# ADC_channel.net
KiCad netlist of a schematic drawn in Altium Designer
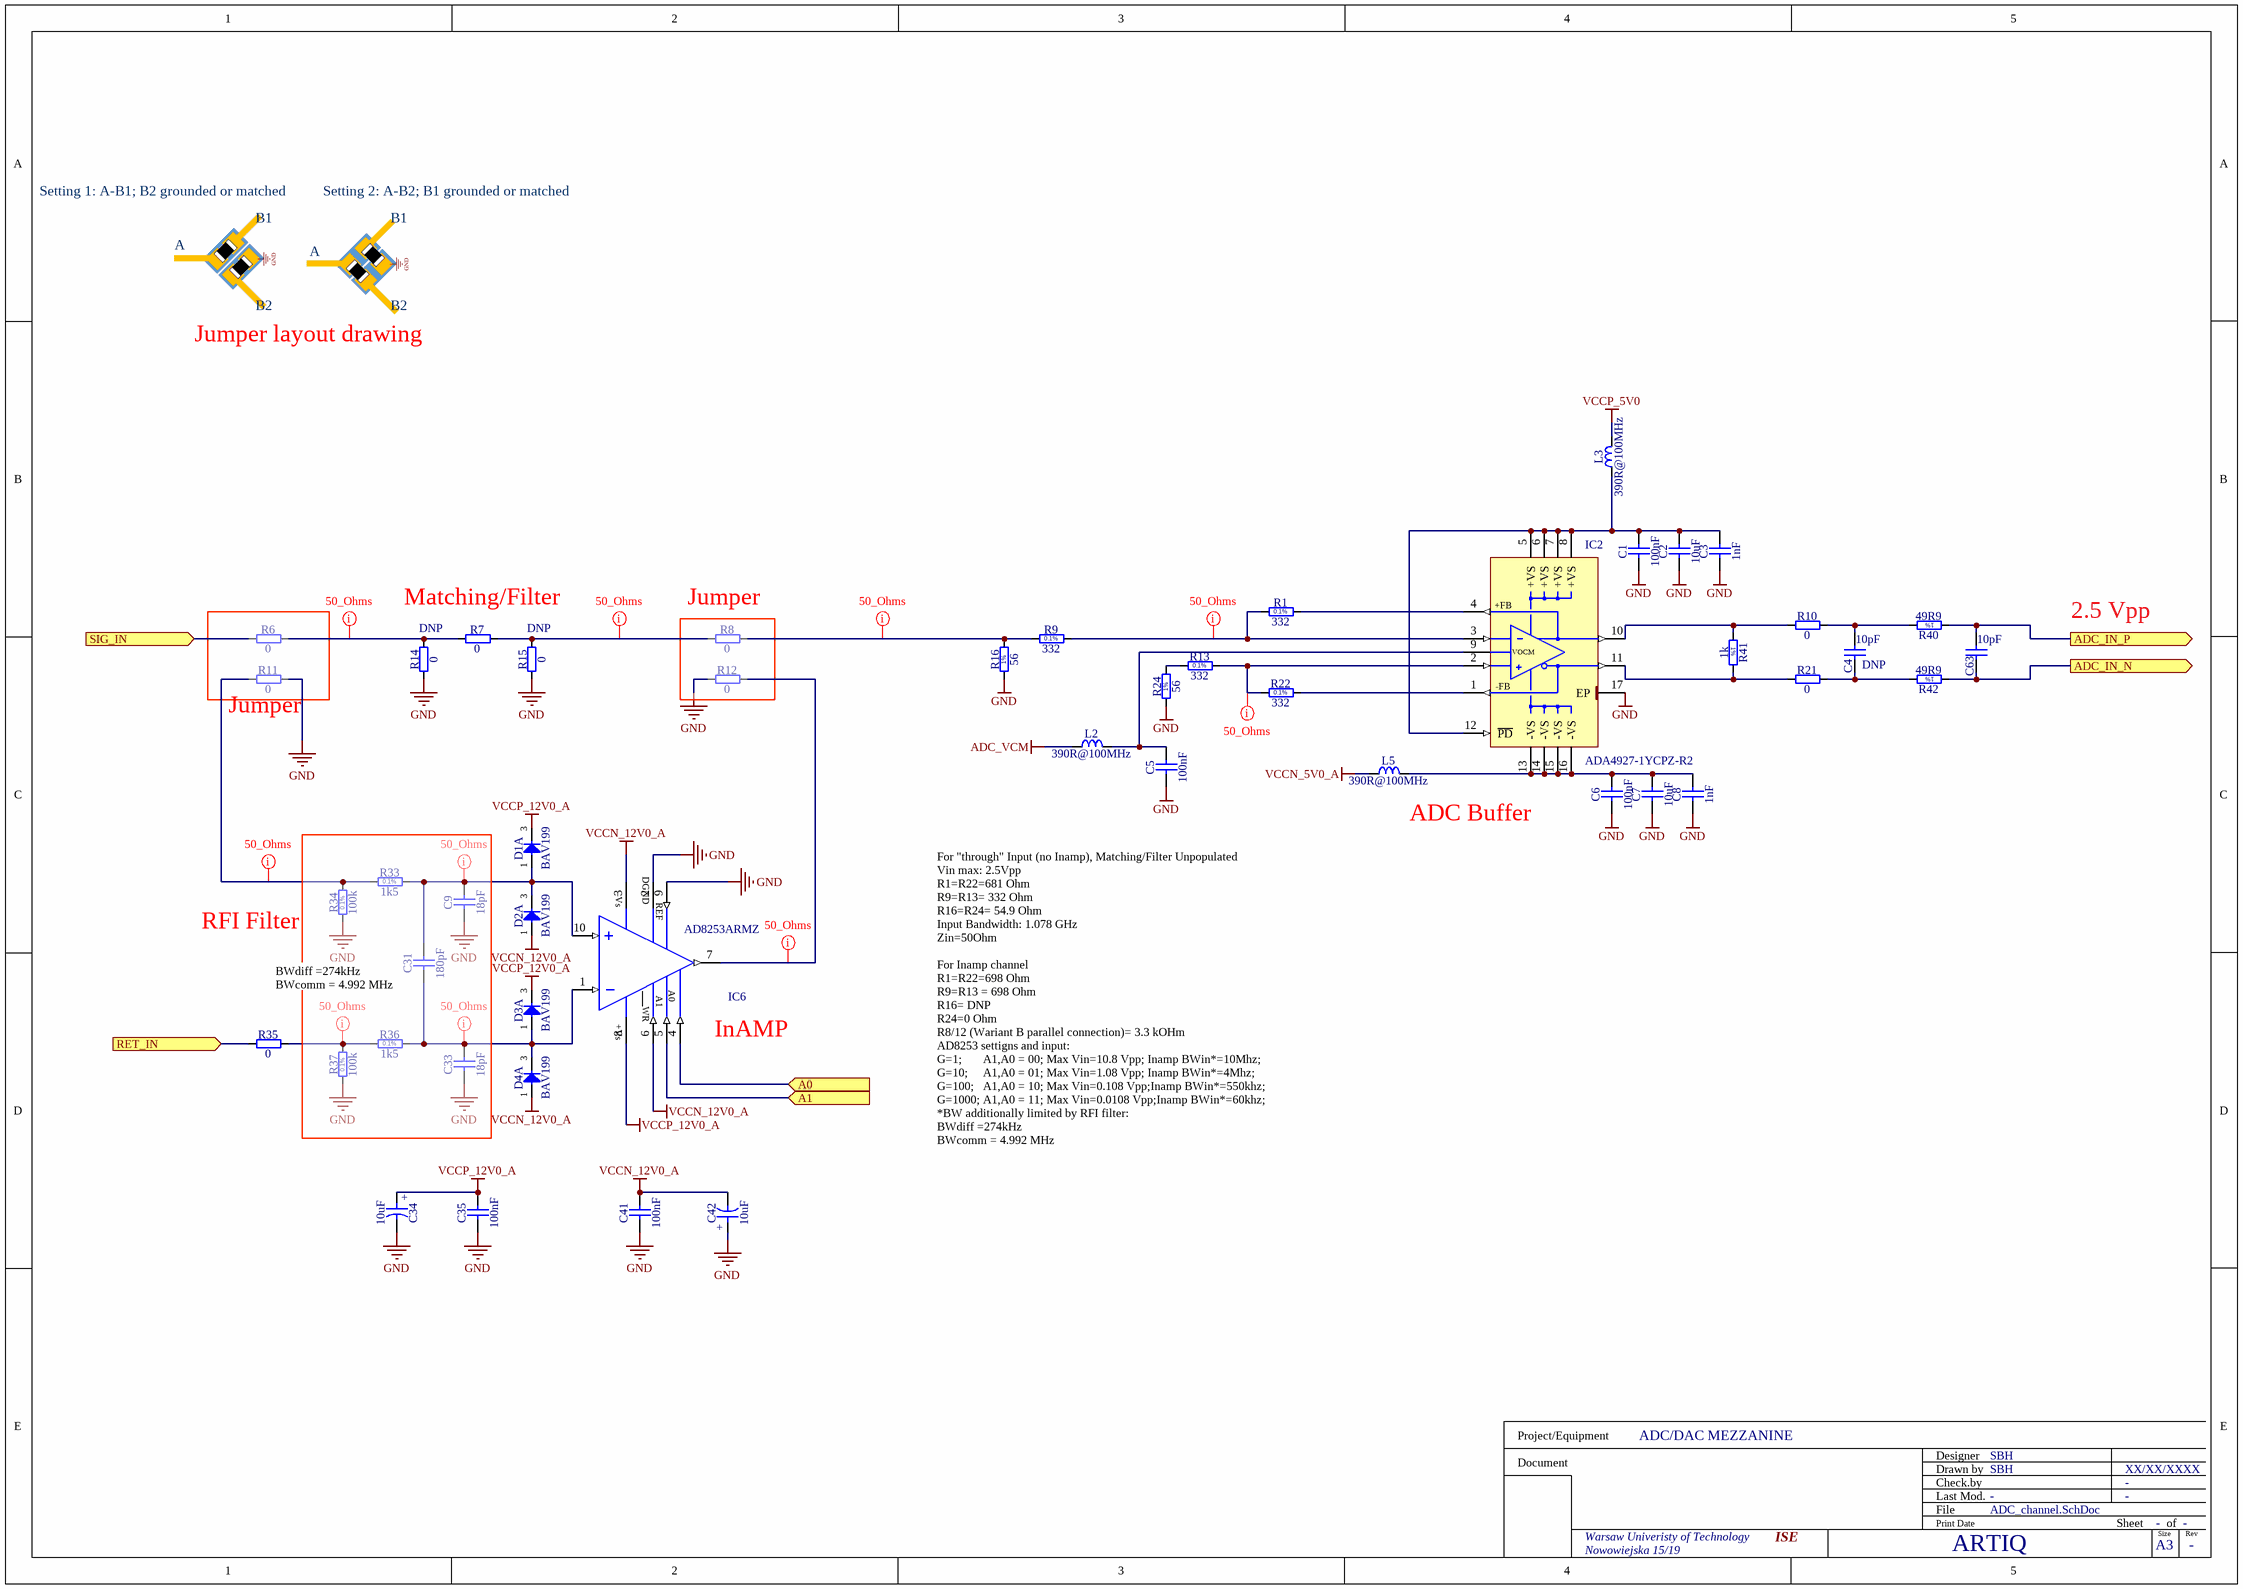
[diagram p0: ADC_channel.SchDoc]

(export (version "E")
  (design (tool "Eeschema 10.0.6"))
  (components
    (comp (ref "C1")
      (value "100nF")
      (footprint "CAPC1005X55N")
      (description "Non-polarised capacitor")
      (fields
        (field (name "PART NUMBER") "CC0402_100NF_16V_10%_X5R")
        (field (name "VOLTAGE") "16V")
        (field (name "AUTHOR") "CERN DEM JLC")
      )
      (libsource (lib "Capacitors") (part "Capacitor - non polarized"))
    )
    (comp (ref "C2")
      (value "10uF")
      (footprint "CAPC1608X87N")
      (description "Non-polarised capacitor")
      (fields
        (field (name "PART NUMBER") "CC0603_10UF_6.3V_20%_X5R")
        (field (name "VOLTAGE") "6.3V")
        (field (name "AUTHOR") "CERN DEM JLC")
      )
      (libsource (lib "Capacitors") (part "Capacitor - non polarized"))
    )
    (comp (ref "C3")
      (value "1nF")
      (footprint "CAPC1005X55N")
      (description "Non-polarised capacitor")
      (fields
        (field (name "PART NUMBER") "CC0402_1NF_50V_10%_X7R")
        (field (name "VOLTAGE") "50V")
        (field (name "AUTHOR") "CERN DEM JLC")
      )
      (libsource (lib "Capacitors") (part "Capacitor - non polarized"))
    )
    (comp (ref "C4")
      (value "10pF")
      (footprint "CAPC1608X87N")
      (description "Non-polarised capacitor")
      (fields
        (field (name "PART NUMBER") "CC0603_10PF_50V_5%_NP0")
        (field (name "VOLTAGE") "50V")
        (field (name "MOUNTED") "DNP")
        (field (name "AUTHOR") "CERN DEM JLC")
      )
      (libsource (lib "Capacitors") (part "Capacitor - non polarized"))
    )
    (comp (ref "C5")
      (value "100nF")
      (footprint "CAPC1005X55N")
      (description "Non-polarised capacitor")
      (fields
        (field (name "PART NUMBER") "CC0402_100NF_16V_10%_X5R")
        (field (name "VOLTAGE") "16V")
        (field (name "AUTHOR") "CERN DEM JLC")
      )
      (libsource (lib "Capacitors") (part "Capacitor - non polarized"))
    )
    (comp (ref "C6")
      (value "100nF")
      (footprint "CAPC1005X55N")
      (description "Non-polarised capacitor")
      (fields
        (field (name "PART NUMBER") "CC0402_100NF_16V_10%_X5R")
        (field (name "VOLTAGE") "16V")
        (field (name "AUTHOR") "CERN DEM JLC")
      )
      (libsource (lib "Capacitors") (part "Capacitor - non polarized"))
    )
    (comp (ref "C7")
      (value "10uF")
      (footprint "CAPC1608X87N")
      (description "Non-polarised capacitor")
      (fields
        (field (name "PART NUMBER") "CC0603_10UF_6.3V_20%_X5R")
        (field (name "VOLTAGE") "6.3V")
        (field (name "AUTHOR") "CERN DEM JLC")
      )
      (libsource (lib "Capacitors") (part "Capacitor - non polarized"))
    )
    (comp (ref "C8")
      (value "1nF")
      (footprint "CAPC1005X55N")
      (description "Non-polarised capacitor")
      (fields
        (field (name "PART NUMBER") "CC0402_1NF_50V_10%_X7R")
        (field (name "VOLTAGE") "50V")
        (field (name "AUTHOR") "CERN DEM JLC")
      )
      (libsource (lib "Capacitors") (part "Capacitor - non polarized"))
    )
    (comp (ref "C9")
      (value "18pF")
      (footprint "CAPC1005X55N")
      (description "Non-polarised capacitor")
      (fields
        (field (name "PART NUMBER") "CC0402_18PF_50V_5%_C0G")
        (field (name "VOLTAGE") "50V")
        (field (name "AUTHOR") "CERN DEM JLC")
      )
      (libsource (lib "Capacitors") (part "Capacitor - non polarized"))
    )
    (comp (ref "C31")
      (value "180pF")
      (footprint "CAPC3216X140N")
      (description "Non-polarised capacitor")
      (fields
        (field (name "PART NUMBER") "CC1206_180PF_50V_5%_NP0")
        (field (name "VOLTAGE") "50V")
        (field (name "AUTHOR") "CERN DEM JLC")
      )
      (libsource (lib "Capacitors") (part "Capacitor - non polarized"))
    )
    (comp (ref "C33")
      (value "18pF")
      (footprint "CAPC1005X55N")
      (description "Non-polarised capacitor")
      (fields
        (field (name "PART NUMBER") "CC0402_18PF_50V_5%_C0G")
        (field (name "VOLTAGE") "50V")
        (field (name "AUTHOR") "CERN DEM JLC")
      )
      (libsource (lib "Capacitors") (part "Capacitor - non polarized"))
    )
    (comp (ref "C34")
      (value "10uF")
      (footprint "CAPMP3216X180N")
      (description "Polarised capacitor")
      (fields
        (field (name "PART NUMBER") "CTE3216-18_10UF_16V_20%_AVX_TCJ")
        (field (name "VOLTAGE") "16V")
        (field (name "AUTHOR") "CERN DEM JLC")
      )
      (libsource (lib "Capacitors") (part "Capacitor - polarized"))
    )
    (comp (ref "C35")
      (value "100nF")
      (footprint "CAPC1005X55N")
      (description "Non-polarised capacitor")
      (fields
        (field (name "PART NUMBER") "CC0402_100NF_16V_10%_X7R")
        (field (name "VOLTAGE") "16V")
        (field (name "AUTHOR") "CERN DEM JLC")
      )
      (libsource (lib "Capacitors") (part "Capacitor - non polarized"))
    )
    (comp (ref "C41")
      (value "100nF")
      (footprint "CAPC1005X55N")
      (description "Non-polarised capacitor")
      (fields
        (field (name "PART NUMBER") "CC0402_100NF_16V_10%_X7R")
        (field (name "VOLTAGE") "16V")
        (field (name "AUTHOR") "CERN DEM JLC")
      )
      (libsource (lib "Capacitors") (part "Capacitor - non polarized"))
    )
    (comp (ref "C42")
      (value "10uF")
      (footprint "CAPMP3216X180N")
      (description "Polarised capacitor")
      (fields
        (field (name "PART NUMBER") "CTE3216-18_10UF_16V_20%_AVX_TCJ")
        (field (name "VOLTAGE") "16V")
        (field (name "AUTHOR") "CERN DEM JLC")
      )
      (libsource (lib "Capacitors") (part "Capacitor - polarized"))
    )
    (comp (ref "C63")
      (value "10pF")
      (footprint "CAPC1608X87N")
      (description "Non-polarised capacitor")
      (fields
        (field (name "PART NUMBER") "CC0603_10PF_50V_5%_NP0")
        (field (name "VOLTAGE") "50V")
        (field (name "AUTHOR") "CERN DEM JLC")
      )
      (libsource (lib "Capacitors") (part "Capacitor - non polarized"))
    )
    (comp (ref "D1")
      (value "BAV199")
      (footprint "SOT95P240X110-3N")
      (description "Serial Diode")
      (fields
        (field (name "VOLTAGE") "75V")
        (field (name "POWER") "250mW")
        (field (name "AUTHOR") "CERN DEM JMW")
      )
      (libsource (lib "ICs And Semiconductors") (part "Diode x2 A1C3_A3C2"))
    )
    (comp (ref "D2")
      (value "BAV199")
      (footprint "SOT95P240X110-3N")
      (description "Serial Diode")
      (fields
        (field (name "VOLTAGE") "75V")
        (field (name "POWER") "250mW")
        (field (name "AUTHOR") "CERN DEM JMW")
      )
      (libsource (lib "ICs And Semiconductors") (part "Diode x2 A1C3_A3C2"))
    )
    (comp (ref "D3")
      (value "BAV199")
      (footprint "SOT95P240X110-3N")
      (description "Serial Diode")
      (fields
        (field (name "VOLTAGE") "75V")
        (field (name "POWER") "250mW")
        (field (name "AUTHOR") "CERN DEM JMW")
      )
      (libsource (lib "ICs And Semiconductors") (part "Diode x2 A1C3_A3C2"))
    )
    (comp (ref "D4")
      (value "BAV199")
      (footprint "SOT95P240X110-3N")
      (description "Serial Diode")
      (fields
        (field (name "VOLTAGE") "75V")
        (field (name "POWER") "250mW")
        (field (name "AUTHOR") "CERN DEM JMW")
      )
      (libsource (lib "ICs And Semiconductors") (part "Diode x2 A1C3_A3C2"))
    )
    (comp (ref "IC2")
      (value "ADA4927-1YCPZ-R2")
      (footprint "QFN50P300X300X100-17N-S145")
      (description "Ultralow Distortion Current Feedback Differential ADC Driver")
      (fields (field (name "MANUFACTURER") "ANALOG DEVICES") (field (name "AUTHOR") "CERN DEM JLC"))
      (libsource (lib "ICs And Semiconductors") (part "ADA4927-1"))
    )
    (comp (ref "IC6")
      (value "AD8253ARMZ")
      (footprint "SOP50P490X110-10N")
      (description "10MHz, 20V/us, G= 1, 10, 100, 1000 iCMOS Programmable Gain Instrumentation Amplifier")
      (fields (field (name "MANUFACTURER") "ANALOG DEVICES") (field (name "AUTHOR") "CERN DEM JLC"))
      (libsource (lib "ICs And Semiconductors") (part "AD8253"))
    )
    (comp (ref "L2")
      (value "390R@100MHz")
      (footprint "INDC1608X95N")
      (description "Inductor")
      (fields
        (field (name "PART NUMBER") "IND0603_TDK_MPZ1608R391A")
        (field (name "POWER") "1.2A")
        (field (name "AUTHOR") "CERN DEM JLC")
      )
      (libsource (lib "Inductors & Transformers") (part "Inductor"))
    )
    (comp (ref "L3")
      (value "390R@100MHz")
      (footprint "INDC1608X95N")
      (description "Inductor")
      (fields
        (field (name "PART NUMBER") "IND0603_TDK_MPZ1608R391A")
        (field (name "POWER") "1.2A")
        (field (name "AUTHOR") "CERN DEM JLC")
      )
      (libsource (lib "") (part "Inductor_1"))
    )
    (comp (ref "L5")
      (value "390R@100MHz")
      (footprint "INDC1608X95N")
      (description "Inductor")
      (fields
        (field (name "PART NUMBER") "IND0603_TDK_MPZ1608R391A")
        (field (name "POWER") "1.2A")
        (field (name "AUTHOR") "CERN DEM JLC")
      )
      (libsource (lib "Inductors & Transformers") (part "Inductor"))
    )
    (comp (ref "R1")
      (value "332")
      (footprint "RESC1608X55N")
      (description "Resistor - 0.1%")
      (fields
        (field (name "PART NUMBER") "R0603_332R_0.1%_0.063W_10PPM")
        (field (name "POWER") "0.063W")
        (field (name "AUTHOR") "CERN DEM JLC")
      )
      (libsource (lib "Resistors") (part "Resistor - 0.1%"))
    )
    (comp (ref "R6")
      (value "0")
      (footprint "RESC1005X40N")
      (description "Resistor")
      (fields
        (field (name "PART NUMBER") "R0402_0R_JUMPER")
        (field (name "MANUFACTURER") "GENERIC")
        (field (name "AUTHOR") "CERN DEM JLC")
      )
      (libsource (lib "Resistors") (part "Resistor"))
    )
    (comp (ref "R7")
      (value "0")
      (footprint "RESC1005X40N")
      (description "Resistor")
      (fields
        (field (name "PART NUMBER") "R0402_0R_JUMPER")
        (field (name "MANUFACTURER") "GENERIC")
        (field (name "AUTHOR") "CERN DEM JLC")
      )
      (libsource (lib "Resistors") (part "Resistor"))
    )
    (comp (ref "R8")
      (value "0")
      (footprint "RESC1005X40N")
      (description "Resistor")
      (fields
        (field (name "PART NUMBER") "R0402_0R_JUMPER")
        (field (name "MANUFACTURER") "GENERIC")
        (field (name "AUTHOR") "CERN DEM JLC")
      )
      (libsource (lib "Resistors") (part "Resistor"))
    )
    (comp (ref "R9")
      (value "332")
      (footprint "RESC1608X55N")
      (description "Resistor - 0.1%")
      (fields
        (field (name "PART NUMBER") "R0603_332R_0.1%_0.063W_10PPM")
        (field (name "POWER") "0.063W")
        (field (name "AUTHOR") "CERN DEM JLC")
      )
      (libsource (lib "Resistors") (part "Resistor - 0.1%"))
    )
    (comp (ref "R10")
      (value "0")
      (footprint "RESC1005X40N")
      (description "Resistor")
      (fields
        (field (name "PART NUMBER") "R0402_0R_JUMPER")
        (field (name "MANUFACTURER") "GENERIC")
        (field (name "AUTHOR") "CERN DEM JLC")
      )
      (libsource (lib "Resistors") (part "Resistor"))
    )
    (comp (ref "R11")
      (value "0")
      (footprint "RESC1005X40N")
      (description "Resistor")
      (fields
        (field (name "PART NUMBER") "R0402_0R_JUMPER")
        (field (name "MANUFACTURER") "GENERIC")
        (field (name "AUTHOR") "CERN DEM JLC")
      )
      (libsource (lib "Resistors") (part "Resistor"))
    )
    (comp (ref "R12")
      (value "0")
      (footprint "RESC1005X40N")
      (description "Resistor")
      (fields
        (field (name "PART NUMBER") "R0402_0R_JUMPER")
        (field (name "MANUFACTURER") "GENERIC")
        (field (name "AUTHOR") "CERN DEM JLC")
      )
      (libsource (lib "Resistors") (part "Resistor"))
    )
    (comp (ref "R13")
      (value "332")
      (footprint "RESC1608X55N")
      (description "Resistor - 0.1%")
      (fields
        (field (name "PART NUMBER") "R0603_332R_0.1%_0.063W_10PPM")
        (field (name "POWER") "0.063W")
        (field (name "AUTHOR") "CERN DEM JLC")
      )
      (libsource (lib "Resistors") (part "Resistor - 0.1%"))
    )
    (comp (ref "R14")
      (value "0")
      (footprint "RESC1005X40N")
      (description "Resistor")
      (fields
        (field (name "PART NUMBER") "R0402_0R_JUMPER")
        (field (name "MANUFACTURER") "GENERIC")
        (field (name "MOUNTED") "DNP")
        (field (name "AUTHOR") "CERN DEM JLC")
      )
      (libsource (lib "Resistors") (part "Resistor"))
    )
    (comp (ref "R15")
      (value "0")
      (footprint "RESC1005X40N")
      (description "Resistor")
      (fields
        (field (name "PART NUMBER") "R0402_0R_JUMPER")
        (field (name "MANUFACTURER") "GENERIC")
        (field (name "MOUNTED") "DNP")
        (field (name "AUTHOR") "CERN DEM JLC")
      )
      (libsource (lib "Resistors") (part "Resistor"))
    )
    (comp (ref "R16")
      (value "56")
      (footprint "RESC1005X40N")
      (description "Resistor - 1%")
      (fields
        (field (name "PART NUMBER") "R0402_56R_1%_0.0625W_100PPM")
        (field (name "POWER") "0.0625W")
        (field (name "AUTHOR") "CERN DEM JLC")
      )
      (libsource (lib "Resistors") (part "Resistor - 1%"))
    )
    (comp (ref "R21")
      (value "0")
      (footprint "RESC1005X40N")
      (description "Resistor")
      (fields
        (field (name "PART NUMBER") "R0402_0R_JUMPER")
        (field (name "MANUFACTURER") "GENERIC")
        (field (name "AUTHOR") "CERN DEM JLC")
      )
      (libsource (lib "Resistors") (part "Resistor"))
    )
    (comp (ref "R22")
      (value "332")
      (footprint "RESC1608X55N")
      (description "Resistor - 0.1%")
      (fields
        (field (name "PART NUMBER") "R0603_332R_0.1%_0.063W_10PPM")
        (field (name "POWER") "0.063W")
        (field (name "AUTHOR") "CERN DEM JLC")
      )
      (libsource (lib "Resistors") (part "Resistor - 0.1%"))
    )
    (comp (ref "R24")
      (value "56")
      (footprint "RESC1005X40N")
      (description "Resistor - 1%")
      (fields
        (field (name "PART NUMBER") "R0402_56R_1%_0.0625W_100PPM")
        (field (name "POWER") "0.0625W")
        (field (name "AUTHOR") "CERN DEM JLC")
      )
      (libsource (lib "Resistors") (part "Resistor - 1%"))
    )
    (comp (ref "R33")
      (value "1k5")
      (footprint "RESC1608X55N")
      (description "Resistor - 0.1%")
      (fields
        (field (name "PART NUMBER") "R0603_1K5_0.1%_0.063W_10PPM")
        (field (name "POWER") "0.063W")
        (field (name "AUTHOR") "CERN DEM JLC")
      )
      (libsource (lib "Resistors") (part "Resistor - 0.1%"))
    )
    (comp (ref "R34")
      (value "100k")
      (footprint "RESC1005X35N")
      (description "Resistor - 0.1%")
      (fields
        (field (name "PART NUMBER") "R0402_100K_0.1%_0.063W_25PPM")
        (field (name "POWER") "0.063W")
        (field (name "AUTHOR") "CERN DEM JMW")
      )
      (libsource (lib "Resistors") (part "Resistor - 0.1%"))
    )
    (comp (ref "R35")
      (value "0")
      (footprint "RESC1005X40N")
      (description "Resistor")
      (fields
        (field (name "PART NUMBER") "R0402_0R_JUMPER")
        (field (name "MANUFACTURER") "GENERIC")
        (field (name "AUTHOR") "CERN DEM JLC")
      )
      (libsource (lib "Resistors") (part "Resistor"))
    )
    (comp (ref "R36")
      (value "1k5")
      (footprint "RESC1608X55N")
      (description "Resistor - 0.1%")
      (fields
        (field (name "PART NUMBER") "R0603_1K5_0.1%_0.063W_10PPM")
        (field (name "POWER") "0.063W")
        (field (name "AUTHOR") "CERN DEM JLC")
      )
      (libsource (lib "Resistors") (part "Resistor - 0.1%"))
    )
    (comp (ref "R37")
      (value "100k")
      (footprint "RESC1005X35N")
      (description "Resistor - 0.1%")
      (fields
        (field (name "PART NUMBER") "R0402_100K_0.1%_0.063W_25PPM")
        (field (name "POWER") "0.063W")
        (field (name "AUTHOR") "CERN DEM JMW")
      )
      (libsource (lib "Resistors") (part "Resistor - 0.1%"))
    )
    (comp (ref "R40")
      (value "49R9")
      (footprint "RESC1005X40N")
      (description "Resistor - 1%")
      (fields
        (field (name "PART NUMBER") "R0402_49R9_1%_0.0625W_100PPM")
        (field (name "POWER") "0.0625W")
        (field (name "AUTHOR") "CERN DEM JLC")
      )
      (libsource (lib "Resistors") (part "Resistor - 1%"))
    )
    (comp (ref "R41")
      (value "1k")
      (footprint "RESC1005X40N")
      (description "Resistor - 1%")
      (fields
        (field (name "PART NUMBER") "R0402_1K_1%_0.0625W_100PPM")
        (field (name "POWER") "0.0625W")
        (field (name "AUTHOR") "CERN DEM JLC")
      )
      (libsource (lib "Resistors") (part "Resistor - 1%"))
    )
    (comp (ref "R42")
      (value "49R9")
      (footprint "RESC1005X40N")
      (description "Resistor - 1%")
      (fields
        (field (name "PART NUMBER") "R0402_49R9_1%_0.0625W_100PPM")
        (field (name "POWER") "0.0625W")
        (field (name "AUTHOR") "CERN DEM JLC")
      )
      (libsource (lib "Resistors") (part "Resistor - 1%"))
    )
  )
  (nets
    (net (code "1") (name "/A0") (class "Default")
      (node (ref "IC6") (pin "4") (pinfunction "A0_4") (pintype "input"))
    )
    (net (code "2") (name "/A1") (class "Default")
      (node (ref "IC6") (pin "5") (pinfunction "A1_5") (pintype "input"))
    )
    (net (code "3") (name "/ADC_IN_N") (class "Default")
      (node (ref "C63") (pin "1") (pinfunction "1_1") (pintype "passive"))
      (node (ref "R42") (pin "1") (pinfunction "1_1") (pintype "passive"))
    )
    (net (code "4") (name "/ADC_IN_P") (class "Default")
      (node (ref "C63") (pin "2") (pinfunction "2_2") (pintype "passive"))
      (node (ref "R40") (pin "1") (pinfunction "1_1") (pintype "passive"))
    )
    (net (code "5") (name "/RET_IN") (class "Default")
      (node (ref "R35") (pin "1") (pinfunction "1_1") (pintype "passive"))
    )
    (net (code "6") (name "/SIG_IN") (class "Default")
      (node (ref "R6") (pin "1") (pinfunction "1_1") (pintype "passive"))
    )
    (net (code "7") (name "ADC_VCM") (class "Default")
      (node (ref "L2") (pin "1") (pinfunction "1_1") (pintype "passive"))
    )
    (net (code "8") (name "GND") (class "Default")
      (node (ref "C1") (pin "1") (pinfunction "1_1") (pintype "passive"))
      (node (ref "C2") (pin "1") (pinfunction "1_1") (pintype "passive"))
      (node (ref "C3") (pin "1") (pinfunction "1_1") (pintype "passive"))
      (node (ref "C33") (pin "1") (pinfunction "1_1") (pintype "passive"))
      (node (ref "C34") (pin "2") (pinfunction "2_2") (pintype "passive"))
      (node (ref "C35") (pin "1") (pinfunction "1_1") (pintype "passive"))
      (node (ref "C41") (pin "1") (pinfunction "1_1") (pintype "passive"))
      (node (ref "C42") (pin "1") (pinfunction "1_1") (pintype "passive"))
      (node (ref "C5") (pin "1") (pinfunction "1_1") (pintype "passive"))
      (node (ref "C6") (pin "1") (pinfunction "1_1") (pintype "passive"))
      (node (ref "C7") (pin "1") (pinfunction "1_1") (pintype "passive"))
      (node (ref "C8") (pin "1") (pinfunction "1_1") (pintype "passive"))
      (node (ref "C9") (pin "1") (pinfunction "1_1") (pintype "passive"))
      (node (ref "IC2") (pin "17") (pinfunction "EP_17") (pintype "power_in"))
      (node (ref "IC6") (pin "2") (pinfunction "DGND_2") (pintype "power_in"))
      (node (ref "IC6") (pin "9") (pinfunction "REF_9") (pintype "input"))
      (node (ref "R11") (pin "2") (pinfunction "2_2") (pintype "passive"))
      (node (ref "R12") (pin "2") (pinfunction "2_2") (pintype "passive"))
      (node (ref "R14") (pin "1") (pinfunction "1_1") (pintype "passive"))
      (node (ref "R15") (pin "1") (pinfunction "1_1") (pintype "passive"))
      (node (ref "R16") (pin "1") (pinfunction "1_1") (pintype "passive"))
      (node (ref "R24") (pin "1") (pinfunction "1_1") (pintype "passive"))
      (node (ref "R34") (pin "1") (pinfunction "1_1") (pintype "passive"))
      (node (ref "R37") (pin "1") (pinfunction "1_1") (pintype "passive"))
    )
    (net (code "9") (name "Net-(C4-Pad1)") (class "Default")
      (node (ref "C4") (pin "1") (pinfunction "1_1") (pintype "passive"))
      (node (ref "R21") (pin "2") (pinfunction "2_2") (pintype "passive"))
      (node (ref "R42") (pin "2") (pinfunction "2_2") (pintype "passive"))
    )
    (net (code "10") (name "Net-(C4-Pad2)") (class "Default")
      (node (ref "C4") (pin "2") (pinfunction "2_2") (pintype "passive"))
      (node (ref "R10") (pin "2") (pinfunction "2_2") (pintype "passive"))
      (node (ref "R40") (pin "2") (pinfunction "2_2") (pintype "passive"))
    )
    (net (code "11") (name "Net-(C6-Pad2)") (class "Default")
      (node (ref "C6") (pin "2") (pinfunction "2_2") (pintype "passive"))
      (node (ref "C7") (pin "2") (pinfunction "2_2") (pintype "passive"))
      (node (ref "C8") (pin "2") (pinfunction "2_2") (pintype "passive"))
      (node (ref "IC2") (pin "13") (pinfunction "-VS_13") (pintype "power_in"))
      (node (ref "IC2") (pin "14") (pinfunction "-VS_14") (pintype "power_in"))
      (node (ref "IC2") (pin "15") (pinfunction "-VS_15") (pintype "power_in"))
      (node (ref "IC2") (pin "16") (pinfunction "-VS_16") (pintype "power_in"))
      (node (ref "L5") (pin "2") (pinfunction "2_2") (pintype "passive"))
    )
    (net (code "12") (name "Net-(D1A-A)") (class "Default")
      (node (ref "C31") (pin "2") (pinfunction "2_2") (pintype "passive"))
      (node (ref "C9") (pin "2") (pinfunction "2_2") (pintype "passive"))
      (node (ref "D1") (pin "1") (pinfunction "A_1") (pintype "passive"))
      (node (ref "D2") (pin "3") (pinfunction "COMAC_3") (pintype "passive"))
      (node (ref "IC6") (pin "10") (pinfunction "+IN_10") (pintype "input"))
      (node (ref "R33") (pin "2") (pinfunction "2_2") (pintype "passive"))
    )
    (net (code "13") (name "Net-(D3A-A)") (class "Default")
      (node (ref "C31") (pin "1") (pinfunction "1_1") (pintype "passive"))
      (node (ref "C33") (pin "2") (pinfunction "2_2") (pintype "passive"))
      (node (ref "D3") (pin "1") (pinfunction "A_1") (pintype "passive"))
      (node (ref "D4") (pin "3") (pinfunction "COMAC_3") (pintype "passive"))
      (node (ref "IC6") (pin "1") (pinfunction "-IN_1") (pintype "input"))
      (node (ref "R36") (pin "2") (pinfunction "2_2") (pintype "passive"))
    )
    (net (code "14") (name "Net-(IC2-+FB)") (class "Default")
      (node (ref "IC2") (pin "4") (pinfunction "+FB_4") (pintype "output"))
      (node (ref "R1") (pin "2") (pinfunction "2_2") (pintype "passive"))
    )
    (net (code "15") (name "Net-(IC2-+IN)") (class "Default")
      (node (ref "IC2") (pin "2") (pinfunction "+IN_2") (pintype "input"))
      (node (ref "R13") (pin "2") (pinfunction "2_2") (pintype "passive"))
      (node (ref "R22") (pin "1") (pinfunction "1_1") (pintype "passive"))
    )
    (net (code "16") (name "Net-(IC2-+OUT)") (class "Default")
      (node (ref "IC2") (pin "10") (pinfunction "+OUT_10") (pintype "output"))
      (node (ref "R10") (pin "1") (pinfunction "1_1") (pintype "passive"))
      (node (ref "R41") (pin "1") (pinfunction "1_1") (pintype "passive"))
    )
    (net (code "17") (name "Net-(IC2--FB)") (class "Default")
      (node (ref "IC2") (pin "1") (pinfunction "-FB_1") (pintype "output"))
      (node (ref "R22") (pin "2") (pinfunction "2_2") (pintype "passive"))
    )
    (net (code "18") (name "Net-(IC2--IN)") (class "Default")
      (node (ref "IC2") (pin "3") (pinfunction "-IN_3") (pintype "input"))
      (node (ref "R1") (pin "1") (pinfunction "1_1") (pintype "passive"))
      (node (ref "R9") (pin "2") (pinfunction "2_2") (pintype "passive"))
    )
    (net (code "19") (name "Net-(IC2--OUT)") (class "Default")
      (node (ref "IC2") (pin "11") (pinfunction "-OUT_11") (pintype "output"))
      (node (ref "R21") (pin "1") (pinfunction "1_1") (pintype "passive"))
      (node (ref "R41") (pin "2") (pinfunction "2_2") (pintype "passive"))
    )
    (net (code "20") (name "Net-(IC2-VOCM)") (class "Default")
      (node (ref "C5") (pin "2") (pinfunction "2_2") (pintype "passive"))
      (node (ref "IC2") (pin "9") (pinfunction "VOCM_9") (pintype "passive"))
      (node (ref "L2") (pin "2") (pinfunction "2_2") (pintype "passive"))
    )
    (net (code "21") (name "Net-(IC2-~{PD})") (class "Default")
      (node (ref "C1") (pin "2") (pinfunction "2_2") (pintype "passive"))
      (node (ref "C2") (pin "2") (pinfunction "2_2") (pintype "passive"))
      (node (ref "C3") (pin "2") (pinfunction "2_2") (pintype "passive"))
      (node (ref "IC2") (pin "12") (pinfunction "~{PD}_12") (pintype "input"))
      (node (ref "IC2") (pin "5") (pinfunction "+VS_5") (pintype "power_in"))
      (node (ref "IC2") (pin "6") (pinfunction "+VS_6") (pintype "power_in"))
      (node (ref "IC2") (pin "7") (pinfunction "+VS_7") (pintype "power_in"))
      (node (ref "IC2") (pin "8") (pinfunction "+VS_8") (pintype "power_in"))
      (node (ref "L3") (pin "1") (pinfunction "1_1") (pintype "passive"))
    )
    (net (code "22") (name "Net-(IC6-OUT)") (class "Default")
      (node (ref "IC6") (pin "7") (pinfunction "OUT_7") (pintype "output"))
      (node (ref "R12") (pin "1") (pinfunction "1_1") (pintype "passive"))
    )
    (net (code "23") (name "Net-(R11-Pad1)") (class "Default")
      (node (ref "R11") (pin "1") (pinfunction "1_1") (pintype "passive"))
      (node (ref "R33") (pin "1") (pinfunction "1_1") (pintype "passive"))
      (node (ref "R34") (pin "2") (pinfunction "2_2") (pintype "passive"))
    )
    (net (code "24") (name "Net-(R13-Pad1)") (class "Default")
      (node (ref "R13") (pin "1") (pinfunction "1_1") (pintype "passive"))
      (node (ref "R24") (pin "2") (pinfunction "2_2") (pintype "passive"))
    )
    (net (code "25") (name "Net-(R14-Pad2)") (class "Default")
      (node (ref "R14") (pin "2") (pinfunction "2_2") (pintype "passive"))
      (node (ref "R6") (pin "2") (pinfunction "2_2") (pintype "passive"))
      (node (ref "R7") (pin "1") (pinfunction "1_1") (pintype "passive"))
    )
    (net (code "26") (name "Net-(R15-Pad2)") (class "Default")
      (node (ref "R15") (pin "2") (pinfunction "2_2") (pintype "passive"))
      (node (ref "R7") (pin "2") (pinfunction "2_2") (pintype "passive"))
      (node (ref "R8") (pin "2") (pinfunction "2_2") (pintype "passive"))
    )
    (net (code "27") (name "Net-(R16-Pad2)") (class "Default")
      (node (ref "R16") (pin "2") (pinfunction "2_2") (pintype "passive"))
      (node (ref "R8") (pin "1") (pinfunction "1_1") (pintype "passive"))
      (node (ref "R9") (pin "1") (pinfunction "1_1") (pintype "passive"))
    )
    (net (code "28") (name "Net-(R35-Pad2)") (class "Default")
      (node (ref "R35") (pin "2") (pinfunction "2_2") (pintype "passive"))
      (node (ref "R36") (pin "1") (pinfunction "1_1") (pintype "passive"))
      (node (ref "R37") (pin "2") (pinfunction "2_2") (pintype "passive"))
    )
    (net (code "29") (name "VCCN_5V0_A") (class "Default")
      (node (ref "L5") (pin "1") (pinfunction "1_1") (pintype "passive"))
    )
    (net (code "30") (name "VCCN_12V0_A") (class "Default")
      (node (ref "C41") (pin "2") (pinfunction "2_2") (pintype "passive"))
      (node (ref "C42") (pin "2") (pinfunction "2_2") (pintype "passive"))
      (node (ref "D2") (pin "1") (pinfunction "A_1") (pintype "passive"))
      (node (ref "D4") (pin "1") (pinfunction "A_1") (pintype "passive"))
      (node (ref "IC6") (pin "3") (pinfunction "-VS_3") (pintype "power_in"))
      (node (ref "IC6") (pin "6") (pinfunction "~{WR}_6") (pintype "input"))
    )
    (net (code "31") (name "VCCP_5V0") (class "Default")
      (node (ref "L3") (pin "2") (pinfunction "2_2") (pintype "passive"))
    )
    (net (code "32") (name "VCCP_12V0_A") (class "Default")
      (node (ref "C34") (pin "1") (pinfunction "1_1") (pintype "passive"))
      (node (ref "C35") (pin "2") (pinfunction "2_2") (pintype "passive"))
      (node (ref "D1") (pin "3") (pinfunction "COMAC_3") (pintype "passive"))
      (node (ref "D3") (pin "3") (pinfunction "COMAC_3") (pintype "passive"))
      (node (ref "IC6") (pin "8") (pinfunction "+VS_8") (pintype "power_in"))
    )
  )
)
